# MAZ000158_-_Diagrama_el_ctrico.net
KiCad netlist of a schematic drawn in Altium Designer
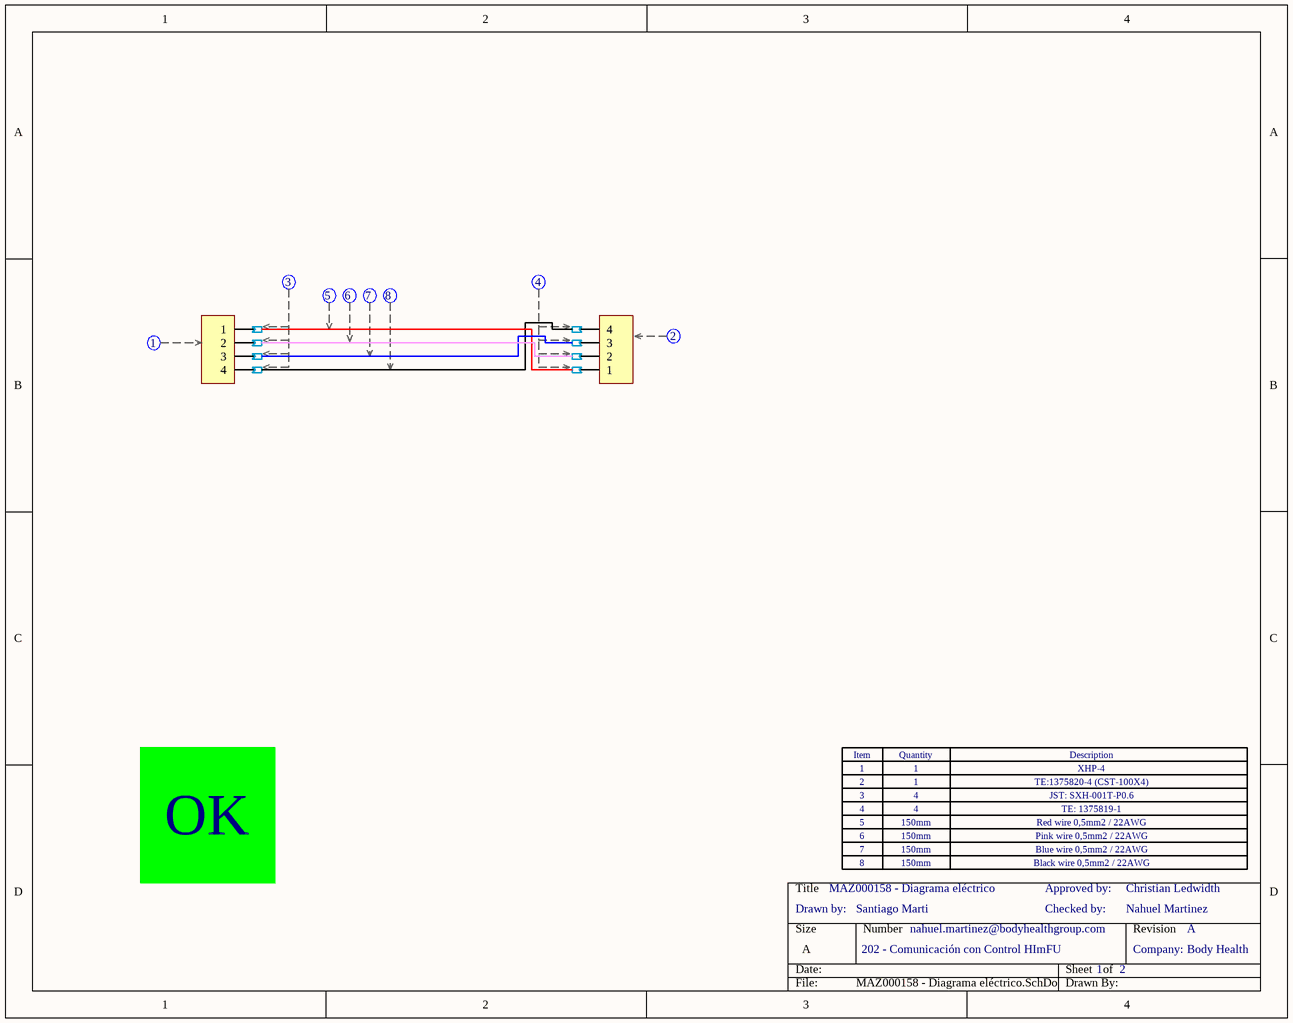
[diagram p0: MAZ000158 - Diagrama eléctrico.SchDoc]

(export (version "E")
  (design (tool "Eeschema 10.0.6"))
  (components
    (comp (ref "Cab1") (value "Cable") (libsource (lib "LibreriaParaPlanos") (part "Cable")))
    (comp (ref "Cab2") (value "Cable") (libsource (lib "LibreriaParaPlanos") (part "Cable")))
    (comp (ref "Cab3") (value "Cable") (libsource (lib "LibreriaParaPlanos") (part "Cable")))
    (comp (ref "Cab4") (value "Cable") (libsource (lib "LibreriaParaPlanos") (part "Cable")))
    (comp (ref "Con1")
      (value "XHP-4")
      (description "CONN HOUSING 2.5MM 4POS")
      (libsource (lib "LibreriaParaPlanos") (part "XHP-4"))
    )
    (comp (ref "Con2")
      (value "CST-100-4")
      (description "CONN RCPT HSNG 4POS CST-100 II")
      (libsource (lib "") (part "CST-100-4_1"))
    )
    (comp (ref "Soc1")
      (value "sock_XHP_SXH-002T-P0.6")
      (description "CONN SOCKET 26-30AWG CRIMP TIN")
      (libsource (lib "LibreriaParaPlanos") (part "sock_XHP_SXH-002T-P0.6"))
    )
    (comp (ref "Soc2")
      (value "sock_CST_1375819-1")
      (description "CONN SOCKET 22-26AWG CRIMP TIN")
      (libsource (lib "LibreriaParaPlanos") (part "sock_CST_1375819-1"))
    )
    (comp (ref "Soc3")
      (value "sock_XHP_SXH-002T-P0.6")
      (description "CONN SOCKET 26-30AWG CRIMP TIN")
      (libsource (lib "LibreriaParaPlanos") (part "sock_XHP_SXH-002T-P0.6"))
    )
    (comp (ref "Soc4")
      (value "sock_CST_1375819-1")
      (description "CONN SOCKET 22-26AWG CRIMP TIN")
      (libsource (lib "LibreriaParaPlanos") (part "sock_CST_1375819-1"))
    )
    (comp (ref "Soc5")
      (value "sock_XHP_SXH-002T-P0.6")
      (description "CONN SOCKET 26-30AWG CRIMP TIN")
      (libsource (lib "LibreriaParaPlanos") (part "sock_XHP_SXH-002T-P0.6"))
    )
    (comp (ref "Soc6")
      (value "sock_CST_1375819-1")
      (description "CONN SOCKET 22-26AWG CRIMP TIN")
      (libsource (lib "LibreriaParaPlanos") (part "sock_CST_1375819-1"))
    )
    (comp (ref "Soc7")
      (value "sock_XHP_SXH-002T-P0.6")
      (description "CONN SOCKET 26-30AWG CRIMP TIN")
      (libsource (lib "LibreriaParaPlanos") (part "sock_XHP_SXH-002T-P0.6"))
    )
    (comp (ref "Soc8")
      (value "sock_CST_1375819-1")
      (description "CONN SOCKET 22-26AWG CRIMP TIN")
      (libsource (lib "LibreriaParaPlanos") (part "sock_CST_1375819-1"))
    )
    (comp (ref "Zoc1")
      (value "Zócalo_Header")
      (description "Header para el zócalo de referencias")
      (libsource (lib "LibreriaParaPlanos") (part "Zócalo_Header"))
    )
    (comp (ref "Zoc2")
      (value "Zócalo_Item")
      (description "Ítem para el zócalo de referencias")
      (libsource (lib "LibreriaParaPlanos") (part "Zócalo_Item"))
    )
    (comp (ref "Zoc3")
      (value "Zócalo_Item")
      (description "Ítem para el zócalo de referencias")
      (libsource (lib "LibreriaParaPlanos") (part "Zócalo_Item"))
    )
    (comp (ref "Zoc4")
      (value "Zócalo_Item")
      (description "Ítem para el zócalo de referencias")
      (libsource (lib "LibreriaParaPlanos") (part "Zócalo_Item"))
    )
    (comp (ref "Zoc5")
      (value "Zócalo_Item")
      (description "Ítem para el zócalo de referencias")
      (libsource (lib "LibreriaParaPlanos") (part "Zócalo_Item"))
    )
    (comp (ref "Zoc6")
      (value "Zócalo_Item")
      (description "Ítem para el zócalo de referencias")
      (libsource (lib "LibreriaParaPlanos") (part "Zócalo_Item"))
    )
    (comp (ref "Zoc7")
      (value "Zócalo_Item")
      (description "Ítem para el zócalo de referencias")
      (libsource (lib "LibreriaParaPlanos") (part "Zócalo_Item"))
    )
    (comp (ref "Zoc8")
      (value "Zócalo_Item")
      (description "Ítem para el zócalo de referencias")
      (libsource (lib "LibreriaParaPlanos") (part "Zócalo_Item"))
    )
    (comp (ref "Zoc9")
      (value "Zócalo_Item")
      (description "Ítem para el zócalo de referencias")
      (libsource (lib "LibreriaParaPlanos") (part "Zócalo_Item"))
    )
  )
  (nets
    (net (code "1") (name "Net-(Con1-Pad1)") (class "Default")
      (node (ref "Con1") (pin "1") (pinfunction "1_1") (pintype "passive"))
      (node (ref "Soc1") (pin "0") (pinfunction "0_0") (pintype "passive"))
    )
    (net (code "2") (name "Net-(Con1-Pad2)") (class "Default")
      (node (ref "Con1") (pin "2") (pinfunction "2_2") (pintype "passive"))
      (node (ref "Soc3") (pin "0") (pinfunction "0_0") (pintype "passive"))
    )
    (net (code "3") (name "Net-(Con1-Pad3)") (class "Default")
      (node (ref "Con1") (pin "3") (pinfunction "3_3") (pintype "passive"))
      (node (ref "Soc5") (pin "0") (pinfunction "0_0") (pintype "passive"))
    )
    (net (code "4") (name "Net-(Con1-Pad4)") (class "Default")
      (node (ref "Con1") (pin "4") (pinfunction "4_4") (pintype "passive"))
      (node (ref "Soc7") (pin "0") (pinfunction "0_0") (pintype "passive"))
    )
    (net (code "5") (name "Net-(Con2-Pad1)") (class "Default")
      (node (ref "Con2") (pin "1") (pinfunction "1_1") (pintype "passive"))
      (node (ref "Soc8") (pin "0") (pinfunction "0_0") (pintype "passive"))
    )
    (net (code "6") (name "Net-(Con2-Pad2)") (class "Default")
      (node (ref "Con2") (pin "2") (pinfunction "2_2") (pintype "passive"))
      (node (ref "Soc6") (pin "0") (pinfunction "0_0") (pintype "passive"))
    )
    (net (code "7") (name "Net-(Con2-Pad3)") (class "Default")
      (node (ref "Con2") (pin "3") (pinfunction "3_3") (pintype "passive"))
      (node (ref "Soc4") (pin "0") (pinfunction "0_0") (pintype "passive"))
    )
    (net (code "8") (name "Net-(Con2-Pad4)") (class "Default")
      (node (ref "Con2") (pin "4") (pinfunction "4_4") (pintype "passive"))
      (node (ref "Soc2") (pin "0") (pinfunction "0_0") (pintype "passive"))
    )
    (net (code "9") (name "Net-(Soc1-Pad1)") (class "Default")
      (node (ref "Soc1") (pin "1") (pinfunction "1_1") (pintype "passive"))
      (node (ref "Soc8") (pin "1") (pinfunction "1_1") (pintype "passive"))
    )
    (net (code "10") (name "Net-(Soc2-Pad1)") (class "Default")
      (node (ref "Soc2") (pin "1") (pinfunction "1_1") (pintype "passive"))
      (node (ref "Soc7") (pin "1") (pinfunction "1_1") (pintype "passive"))
    )
    (net (code "11") (name "Net-(Soc3-Pad1)") (class "Default")
      (node (ref "Soc3") (pin "1") (pinfunction "1_1") (pintype "passive"))
      (node (ref "Soc6") (pin "1") (pinfunction "1_1") (pintype "passive"))
    )
    (net (code "12") (name "Net-(Soc4-Pad1)") (class "Default")
      (node (ref "Soc4") (pin "1") (pinfunction "1_1") (pintype "passive"))
      (node (ref "Soc5") (pin "1") (pinfunction "1_1") (pintype "passive"))
    )
  )
)
